# backplane.net
KiCad netlist of a schematic drawn in EAGLE
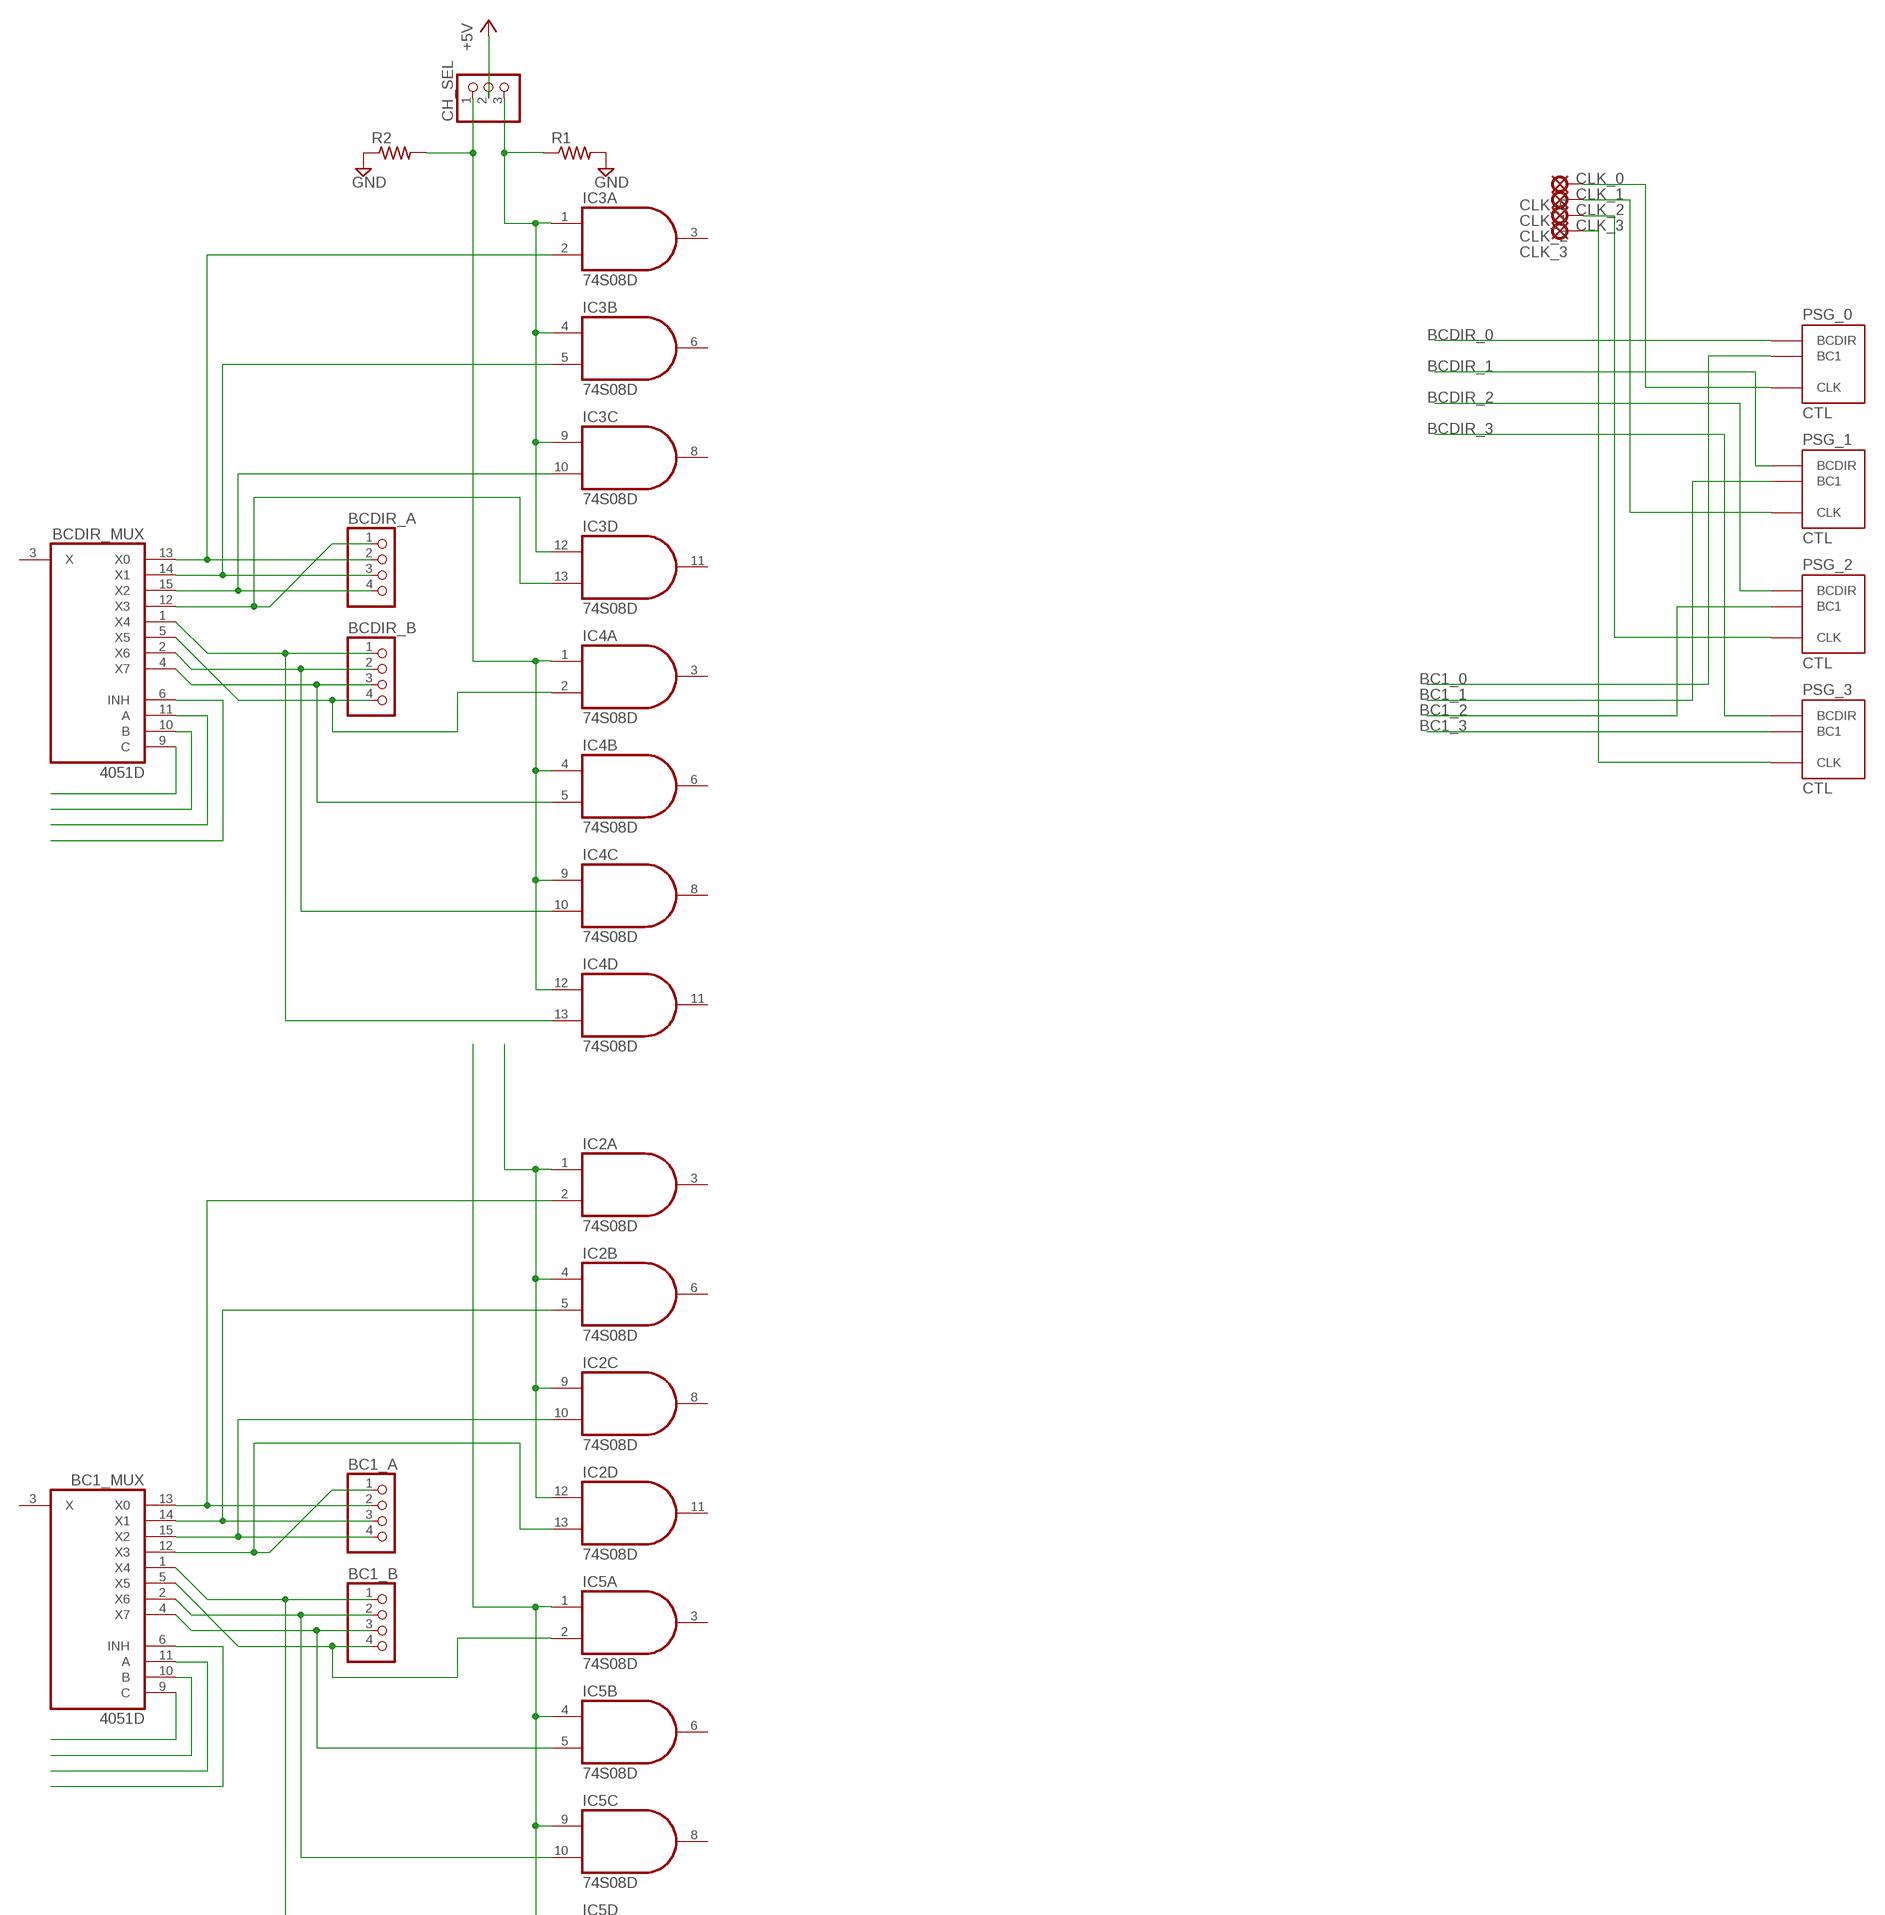
[diagram p0: schematic, sheet 1, part 1 of 3]
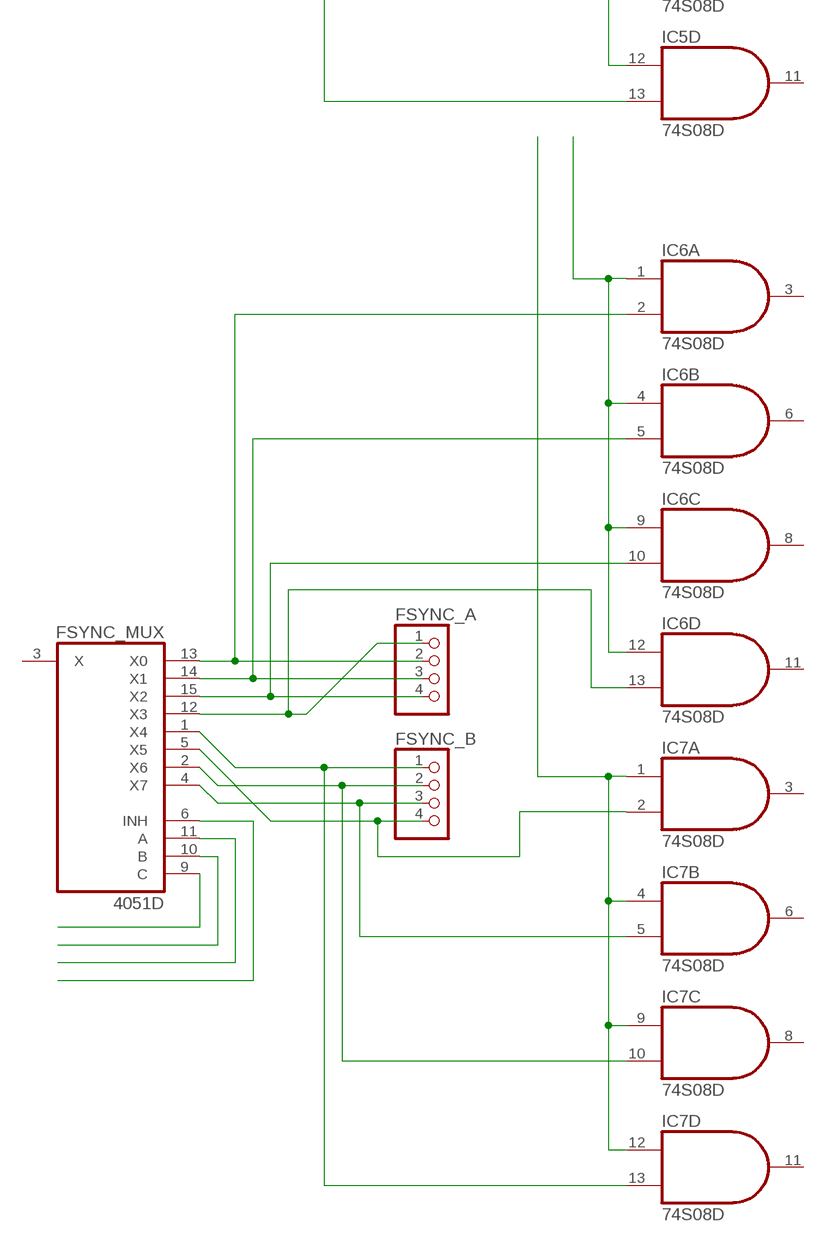
[diagram p1: schematic, sheet 1, part 2 of 3]
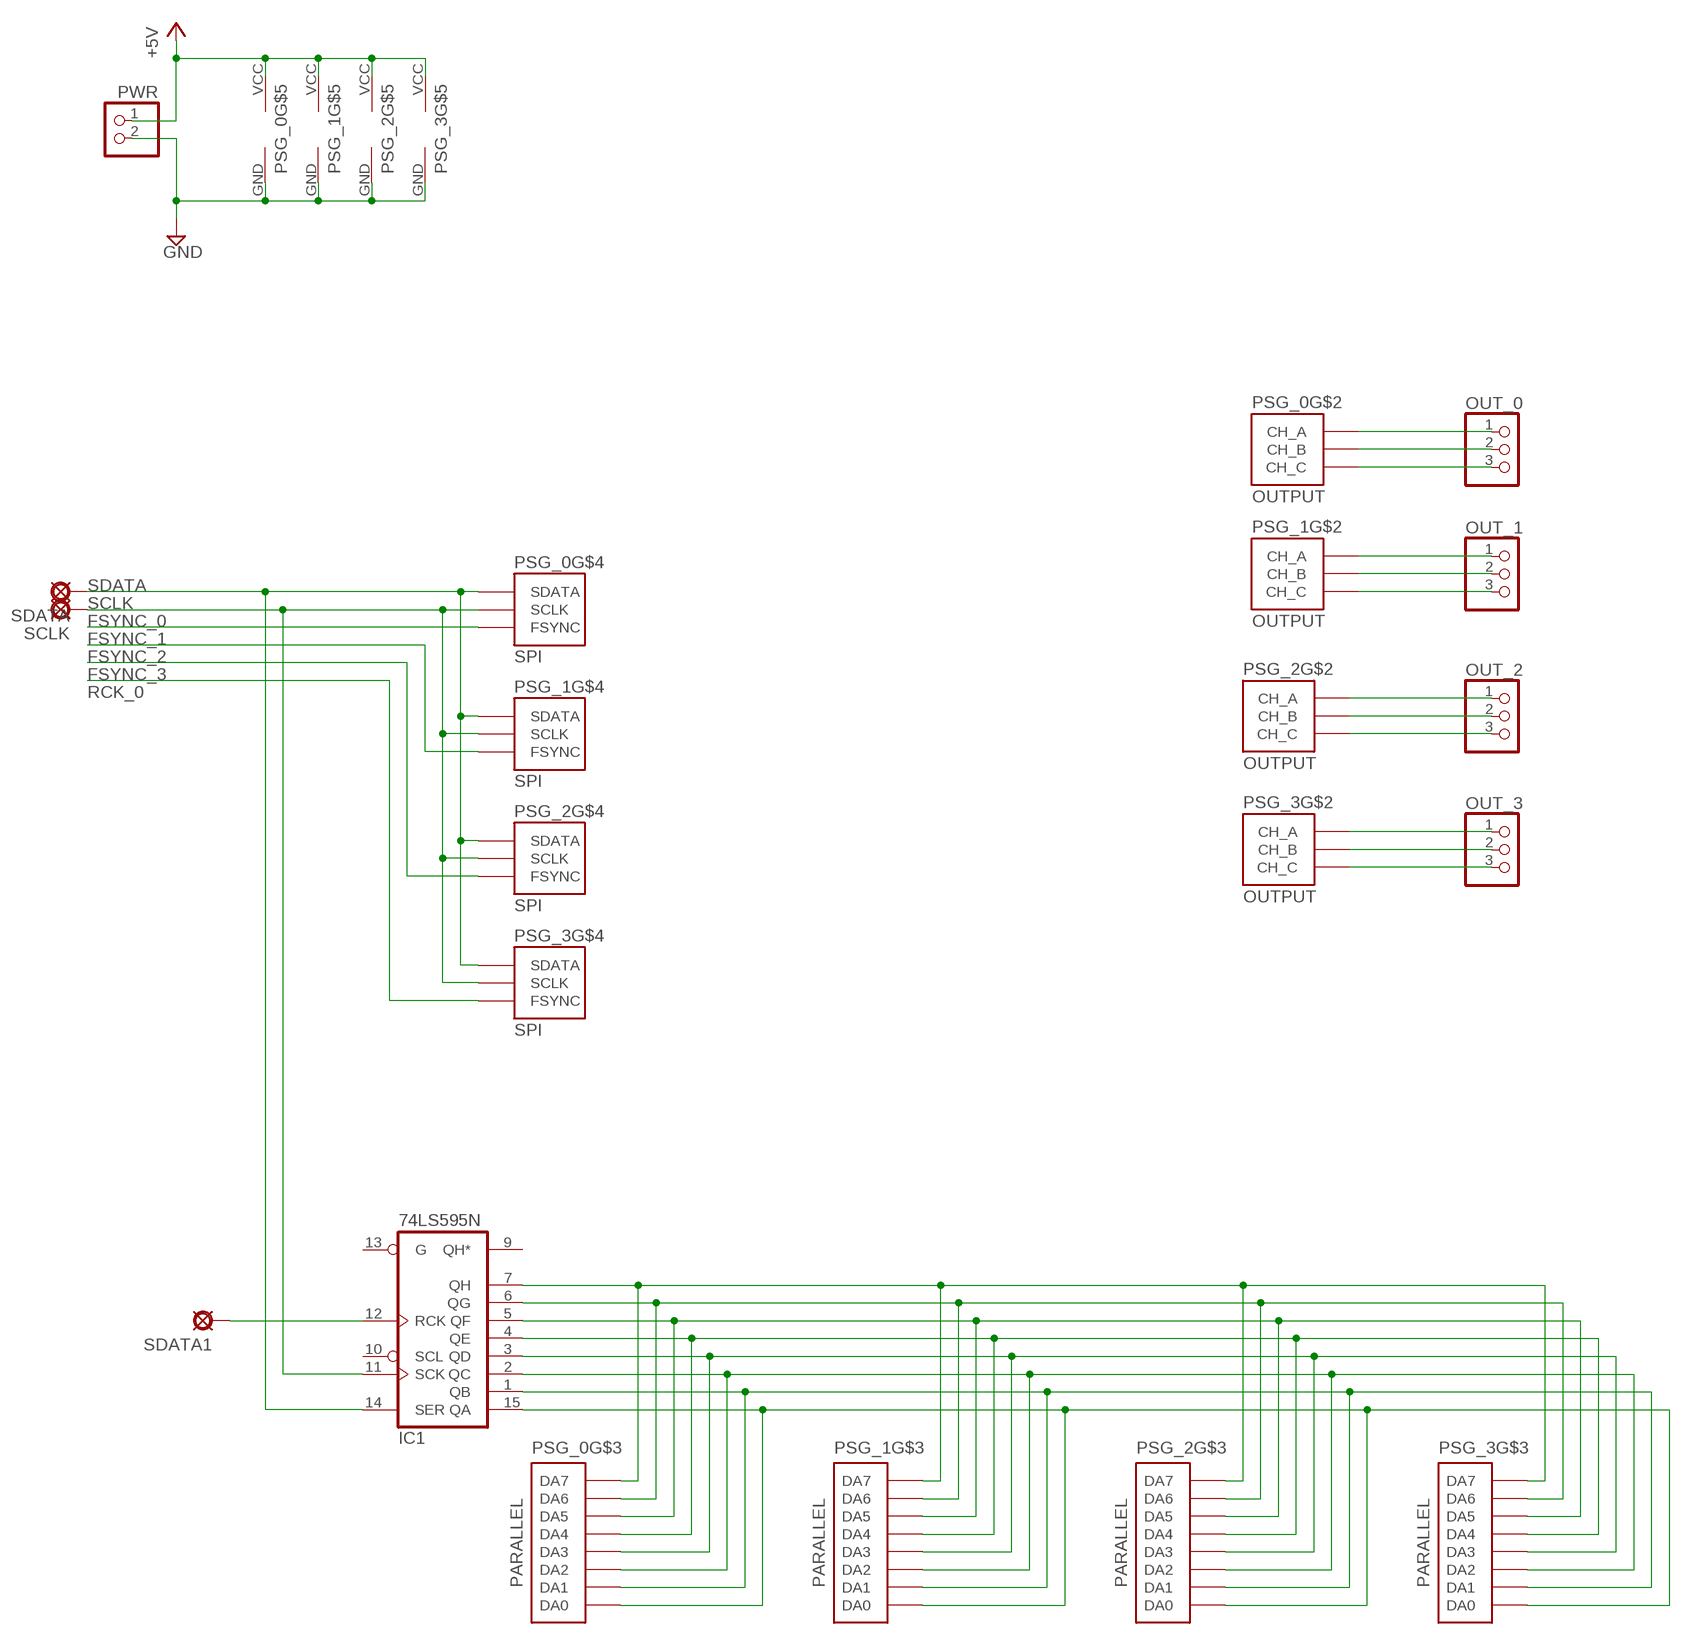
[diagram p2: schematic, sheet 1, part 3 of 3]

(export (version "E")
  (design (tool "Eeschema 10.0.6"))
  (components
    (comp (ref "BC1_A")
      (value "PINHD-1X4")
      (footprint "eagle-import:1X04")
      (libsource (lib "eagle-import") (part "PINHD-1X4"))
    )
    (comp (ref "BC1_B")
      (value "PINHD-1X4")
      (footprint "eagle-import:1X04")
      (libsource (lib "eagle-import") (part "PINHD-1X4"))
    )
    (comp (ref "BC1_MUX")
      (value "4051D")
      (footprint "eagle-import:SO16")
      (libsource (lib "eagle-import") (part "4051D"))
    )
    (comp (ref "BCDIR_A")
      (value "PINHD-1X4")
      (footprint "eagle-import:1X04")
      (libsource (lib "eagle-import") (part "PINHD-1X4"))
    )
    (comp (ref "BCDIR_B")
      (value "PINHD-1X4")
      (footprint "eagle-import:1X04")
      (libsource (lib "eagle-import") (part "PINHD-1X4"))
    )
    (comp (ref "BCDIR_MUX")
      (value "4051D")
      (footprint "eagle-import:SO16")
      (libsource (lib "eagle-import") (part "4051D"))
    )
    (comp (ref "CH_SEL")
      (value "PINHD-1X3")
      (footprint "eagle-import:1X03")
      (libsource (lib "eagle-import") (part "PINHD-1X3"))
    )
    (comp (ref "CLK_0")
      (value "PAD")
      (footprint "eagle-import:SQUARE")
      (libsource (lib "eagle-import") (part "PAD"))
    )
    (comp (ref "CLK_1")
      (value "PAD")
      (footprint "eagle-import:SQUARE")
      (libsource (lib "eagle-import") (part "PAD"))
    )
    (comp (ref "CLK_2")
      (value "PAD")
      (footprint "eagle-import:SQUARE")
      (libsource (lib "eagle-import") (part "PAD"))
    )
    (comp (ref "CLK_3")
      (value "PAD")
      (footprint "eagle-import:SQUARE")
      (libsource (lib "eagle-import") (part "PAD"))
    )
    (comp (ref "FSYNC_A")
      (value "PINHD-1X4")
      (footprint "eagle-import:1X04")
      (libsource (lib "eagle-import") (part "PINHD-1X4"))
    )
    (comp (ref "FSYNC_B")
      (value "PINHD-1X4")
      (footprint "eagle-import:1X04")
      (libsource (lib "eagle-import") (part "PINHD-1X4"))
    )
    (comp (ref "FSYNC_MUX")
      (value "4051D")
      (footprint "eagle-import:SO16")
      (libsource (lib "eagle-import") (part "4051D"))
    )
    (comp (ref "IC1")
      (value "74LS595N")
      (footprint "eagle-import:DIL16")
      (libsource (lib "eagle-import") (part "74595NLS"))
    )
    (comp (ref "IC2")
      (value "74S08D")
      (footprint "eagle-import:SO14")
      (libsource (lib "eagle-import") (part "7408DS"))
    )
    (comp (ref "IC3")
      (value "74S08D")
      (footprint "eagle-import:SO14")
      (libsource (lib "eagle-import") (part "7408DS"))
    )
    (comp (ref "IC4")
      (value "74S08D")
      (footprint "eagle-import:SO14")
      (libsource (lib "eagle-import") (part "7408DS"))
    )
    (comp (ref "IC5")
      (value "74S08D")
      (footprint "eagle-import:SO14")
      (libsource (lib "eagle-import") (part "7408DS"))
    )
    (comp (ref "IC6")
      (value "74S08D")
      (footprint "eagle-import:SO14")
      (libsource (lib "eagle-import") (part "7408DS"))
    )
    (comp (ref "IC7")
      (value "74S08D")
      (footprint "eagle-import:SO14")
      (libsource (lib "eagle-import") (part "7408DS"))
    )
    (comp (ref "OUT_0")
      (value "PINHD-1X3")
      (footprint "eagle-import:1X03")
      (libsource (lib "eagle-import") (part "PINHD-1X3"))
    )
    (comp (ref "OUT_1")
      (value "PINHD-1X3")
      (footprint "eagle-import:1X03")
      (libsource (lib "eagle-import") (part "PINHD-1X3"))
    )
    (comp (ref "OUT_2")
      (value "PINHD-1X3")
      (footprint "eagle-import:1X03")
      (libsource (lib "eagle-import") (part "PINHD-1X3"))
    )
    (comp (ref "OUT_3")
      (value "PINHD-1X3")
      (footprint "eagle-import:1X03")
      (libsource (lib "eagle-import") (part "PINHD-1X3"))
    )
    (comp (ref "PSG_0")
      (value "PSG_DAUGHTER")
      (footprint "eagle-import:PSG_DAUGHTER")
      (libsource (lib "eagle-import") (part "PSG_DAUGHTER"))
    )
    (comp (ref "PSG_1")
      (value "PSG_DAUGHTER")
      (footprint "eagle-import:PSG_DAUGHTER")
      (libsource (lib "eagle-import") (part "PSG_DAUGHTER"))
    )
    (comp (ref "PSG_2")
      (value "PSG_DAUGHTER")
      (footprint "eagle-import:PSG_DAUGHTER")
      (libsource (lib "eagle-import") (part "PSG_DAUGHTER"))
    )
    (comp (ref "PSG_3")
      (value "PSG_DAUGHTER")
      (footprint "eagle-import:PSG_DAUGHTER")
      (libsource (lib "eagle-import") (part "PSG_DAUGHTER"))
    )
    (comp (ref "PWR")
      (value "PINHD-1X2")
      (footprint "eagle-import:1X02")
      (libsource (lib "eagle-import") (part "PINHD-1X2"))
    )
    (comp (ref "R1")
      (value "6MM.3")
      (footprint "eagle-import:R0207_3")
      (libsource (lib "eagle-import") (part "6MM.3"))
    )
    (comp (ref "R2")
      (value "6MM.3")
      (footprint "eagle-import:R0207_3")
      (libsource (lib "eagle-import") (part "6MM.3"))
    )
    (comp (ref "SCLK")
      (value "PAD")
      (footprint "eagle-import:SQUARE")
      (libsource (lib "eagle-import") (part "PAD"))
    )
    (comp (ref "SDATA")
      (value "PAD")
      (footprint "eagle-import:SQUARE")
      (libsource (lib "eagle-import") (part "PAD"))
    )
    (comp (ref "SDATA1")
      (value "PAD")
      (footprint "eagle-import:SQUARE")
      (libsource (lib "eagle-import") (part "PAD"))
    )
  )
  (nets
    (net (code "1") (name "+5V") (class "Default")
      (node (ref "CH_SEL") (pin "2") (pinfunction "2_2") (pintype "passive"))
      (node (ref "PSG_0") (pin "VCC") (pinfunction "VCC_VCC") (pintype "power_in"))
      (node (ref "PSG_1") (pin "VCC") (pinfunction "VCC_VCC") (pintype "power_in"))
      (node (ref "PSG_2") (pin "VCC") (pinfunction "VCC_VCC") (pintype "power_in"))
      (node (ref "PSG_3") (pin "VCC") (pinfunction "VCC_VCC") (pintype "power_in"))
      (node (ref "PWR") (pin "1") (pinfunction "1_1") (pintype "passive"))
    )
    (net (code "2") (name "/BC1_0") (class "Default")
      (node (ref "PSG_0") (pin "BC1") (pinfunction "BC1_BC1") (pintype "input"))
    )
    (net (code "3") (name "/BC1_1") (class "Default")
      (node (ref "PSG_1") (pin "BC1") (pinfunction "BC1_BC1") (pintype "input"))
    )
    (net (code "4") (name "/BC1_2") (class "Default")
      (node (ref "PSG_2") (pin "BC1") (pinfunction "BC1_BC1") (pintype "input"))
    )
    (net (code "5") (name "/BC1_3") (class "Default")
      (node (ref "PSG_3") (pin "BC1") (pinfunction "BC1_BC1") (pintype "input"))
    )
    (net (code "6") (name "/BCDIR_0") (class "Default")
      (node (ref "PSG_0") (pin "BCDIR") (pinfunction "BCDIR_BCDIR") (pintype "input"))
    )
    (net (code "7") (name "/BCDIR_1") (class "Default")
      (node (ref "PSG_1") (pin "BCDIR") (pinfunction "BCDIR_BCDIR") (pintype "input"))
    )
    (net (code "8") (name "/BCDIR_2") (class "Default")
      (node (ref "PSG_2") (pin "BCDIR") (pinfunction "BCDIR_BCDIR") (pintype "input"))
    )
    (net (code "9") (name "/BCDIR_3") (class "Default")
      (node (ref "PSG_3") (pin "BCDIR") (pinfunction "BCDIR_BCDIR") (pintype "input"))
    )
    (net (code "10") (name "/CH_A") (class "Default")
      (node (ref "CH_SEL") (pin "3") (pinfunction "3_3") (pintype "passive"))
      (node (ref "IC2") (pin "1") (pinfunction "I0_1") (pintype "input"))
      (node (ref "IC2") (pin "12") (pinfunction "I0_12") (pintype "input"))
      (node (ref "IC2") (pin "4") (pinfunction "I0_4") (pintype "input"))
      (node (ref "IC2") (pin "9") (pinfunction "I0_9") (pintype "input"))
      (node (ref "IC3") (pin "1") (pinfunction "I0_1") (pintype "input"))
      (node (ref "IC3") (pin "12") (pinfunction "I0_12") (pintype "input"))
      (node (ref "IC3") (pin "4") (pinfunction "I0_4") (pintype "input"))
      (node (ref "IC3") (pin "9") (pinfunction "I0_9") (pintype "input"))
      (node (ref "IC6") (pin "1") (pinfunction "I0_1") (pintype "input"))
      (node (ref "IC6") (pin "12") (pinfunction "I0_12") (pintype "input"))
      (node (ref "IC6") (pin "4") (pinfunction "I0_4") (pintype "input"))
      (node (ref "IC6") (pin "9") (pinfunction "I0_9") (pintype "input"))
      (node (ref "R1") (pin "1") (pinfunction "1_1") (pintype "passive"))
    )
    (net (code "11") (name "/CH_B") (class "Default")
      (node (ref "CH_SEL") (pin "1") (pinfunction "1_1") (pintype "passive"))
      (node (ref "IC4") (pin "1") (pinfunction "I0_1") (pintype "input"))
      (node (ref "IC4") (pin "12") (pinfunction "I0_12") (pintype "input"))
      (node (ref "IC4") (pin "4") (pinfunction "I0_4") (pintype "input"))
      (node (ref "IC4") (pin "9") (pinfunction "I0_9") (pintype "input"))
      (node (ref "IC5") (pin "1") (pinfunction "I0_1") (pintype "input"))
      (node (ref "IC5") (pin "12") (pinfunction "I0_12") (pintype "input"))
      (node (ref "IC5") (pin "4") (pinfunction "I0_4") (pintype "input"))
      (node (ref "IC5") (pin "9") (pinfunction "I0_9") (pintype "input"))
      (node (ref "IC7") (pin "1") (pinfunction "I0_1") (pintype "input"))
      (node (ref "IC7") (pin "12") (pinfunction "I0_12") (pintype "input"))
      (node (ref "IC7") (pin "4") (pinfunction "I0_4") (pintype "input"))
      (node (ref "IC7") (pin "9") (pinfunction "I0_9") (pintype "input"))
      (node (ref "R2") (pin "2") (pinfunction "2_2") (pintype "passive"))
    )
    (net (code "12") (name "/CLK_0") (class "Default")
      (node (ref "CLK_0") (pin "1") (pinfunction "PAD_1") (pintype "passive"))
      (node (ref "PSG_0") (pin "CLK") (pinfunction "CLK_CLK") (pintype "input"))
    )
    (net (code "13") (name "/CLK_1") (class "Default")
      (node (ref "CLK_1") (pin "1") (pinfunction "PAD_1") (pintype "passive"))
      (node (ref "PSG_1") (pin "CLK") (pinfunction "CLK_CLK") (pintype "input"))
    )
    (net (code "14") (name "/CLK_2") (class "Default")
      (node (ref "CLK_2") (pin "1") (pinfunction "PAD_1") (pintype "passive"))
      (node (ref "PSG_2") (pin "CLK") (pinfunction "CLK_CLK") (pintype "input"))
    )
    (net (code "15") (name "/CLK_3") (class "Default")
      (node (ref "CLK_3") (pin "1") (pinfunction "PAD_1") (pintype "passive"))
      (node (ref "PSG_3") (pin "CLK") (pinfunction "CLK_CLK") (pintype "input"))
    )
    (net (code "16") (name "/FSYNC_0") (class "Default")
      (node (ref "PSG_0") (pin "FSYNC") (pinfunction "FSYNC_FSYNC") (pintype "input"))
    )
    (net (code "17") (name "/FSYNC_1") (class "Default")
      (node (ref "PSG_1") (pin "FSYNC") (pinfunction "FSYNC_FSYNC") (pintype "input"))
    )
    (net (code "18") (name "/FSYNC_2") (class "Default")
      (node (ref "PSG_2") (pin "FSYNC") (pinfunction "FSYNC_FSYNC") (pintype "input"))
    )
    (net (code "19") (name "/FSYNC_3") (class "Default")
      (node (ref "PSG_3") (pin "FSYNC") (pinfunction "FSYNC_FSYNC") (pintype "input"))
    )
    (net (code "20") (name "/RCK_0") (class "Default")
      (node (ref "IC1") (pin "12") (pinfunction "RCK_12") (pintype "input"))
      (node (ref "SDATA1") (pin "1") (pinfunction "PAD_1") (pintype "passive"))
    )
    (net (code "21") (name "/SCLK") (class "Default")
      (node (ref "IC1") (pin "11") (pinfunction "SCK_11") (pintype "input"))
      (node (ref "PSG_0") (pin "SCLK") (pinfunction "SCLK_SCLK") (pintype "input"))
      (node (ref "PSG_1") (pin "SCLK") (pinfunction "SCLK_SCLK") (pintype "input"))
      (node (ref "PSG_2") (pin "SCLK") (pinfunction "SCLK_SCLK") (pintype "input"))
      (node (ref "PSG_3") (pin "SCLK") (pinfunction "SCLK_SCLK") (pintype "input"))
      (node (ref "SCLK") (pin "1") (pinfunction "PAD_1") (pintype "passive"))
    )
    (net (code "22") (name "/SDATA") (class "Default")
      (node (ref "IC1") (pin "14") (pinfunction "SER_14") (pintype "input"))
      (node (ref "PSG_0") (pin "SDATA") (pinfunction "SDATA_SDATA") (pintype "bidirectional"))
      (node (ref "PSG_1") (pin "SDATA") (pinfunction "SDATA_SDATA") (pintype "bidirectional"))
      (node (ref "PSG_2") (pin "SDATA") (pinfunction "SDATA_SDATA") (pintype "bidirectional"))
      (node (ref "PSG_3") (pin "SDATA") (pinfunction "SDATA_SDATA") (pintype "bidirectional"))
      (node (ref "SDATA") (pin "1") (pinfunction "PAD_1") (pintype "passive"))
    )
    (net (code "23") (name "GND") (class "Default")
      (node (ref "PSG_0") (pin "GND") (pinfunction "GND_GND") (pintype "power_in"))
      (node (ref "PSG_1") (pin "GND") (pinfunction "GND_GND") (pintype "power_in"))
      (node (ref "PSG_2") (pin "GND") (pinfunction "GND_GND") (pintype "power_in"))
      (node (ref "PSG_3") (pin "GND") (pinfunction "GND_GND") (pintype "power_in"))
      (node (ref "PWR") (pin "2") (pinfunction "2_2") (pintype "passive"))
      (node (ref "R1") (pin "2") (pinfunction "2_2") (pintype "passive"))
      (node (ref "R2") (pin "1") (pinfunction "1_1") (pintype "passive"))
    )
    (net (code "24") (name "Net-(BC1_MUXA-X0)") (class "Default")
      (node (ref "BC1_A") (pin "2") (pinfunction "2_2") (pintype "passive"))
      (node (ref "BC1_MUX") (pin "13") (pinfunction "X0_13") (pintype "bidirectional"))
      (node (ref "IC2") (pin "2") (pinfunction "I1_2") (pintype "input"))
    )
    (net (code "25") (name "Net-(BC1_MUXA-X1)") (class "Default")
      (node (ref "BC1_A") (pin "3") (pinfunction "3_3") (pintype "passive"))
      (node (ref "BC1_MUX") (pin "14") (pinfunction "X1_14") (pintype "bidirectional"))
      (node (ref "IC2") (pin "5") (pinfunction "I1_5") (pintype "input"))
    )
    (net (code "26") (name "Net-(BC1_MUXA-X2)") (class "Default")
      (node (ref "BC1_A") (pin "4") (pinfunction "4_4") (pintype "passive"))
      (node (ref "BC1_MUX") (pin "15") (pinfunction "X2_15") (pintype "bidirectional"))
      (node (ref "IC2") (pin "10") (pinfunction "I1_10") (pintype "input"))
    )
    (net (code "27") (name "Net-(BC1_MUXA-X3)") (class "Default")
      (node (ref "BC1_A") (pin "1") (pinfunction "1_1") (pintype "passive"))
      (node (ref "BC1_MUX") (pin "12") (pinfunction "X3_12") (pintype "bidirectional"))
      (node (ref "IC2") (pin "13") (pinfunction "I1_13") (pintype "input"))
    )
    (net (code "28") (name "Net-(BC1_MUXA-X4)") (class "Default")
      (node (ref "BC1_B") (pin "1") (pinfunction "1_1") (pintype "passive"))
      (node (ref "BC1_MUX") (pin "1") (pinfunction "X4_1") (pintype "bidirectional"))
      (node (ref "IC5") (pin "13") (pinfunction "I1_13") (pintype "input"))
    )
    (net (code "29") (name "Net-(BC1_MUXA-X5)") (class "Default")
      (node (ref "BC1_B") (pin "4") (pinfunction "4_4") (pintype "passive"))
      (node (ref "BC1_MUX") (pin "5") (pinfunction "X5_5") (pintype "bidirectional"))
      (node (ref "IC5") (pin "2") (pinfunction "I1_2") (pintype "input"))
    )
    (net (code "30") (name "Net-(BC1_MUXA-X6)") (class "Default")
      (node (ref "BC1_B") (pin "2") (pinfunction "2_2") (pintype "passive"))
      (node (ref "BC1_MUX") (pin "2") (pinfunction "X6_2") (pintype "bidirectional"))
      (node (ref "IC5") (pin "10") (pinfunction "I1_10") (pintype "input"))
    )
    (net (code "31") (name "Net-(BC1_MUXA-X7)") (class "Default")
      (node (ref "BC1_B") (pin "3") (pinfunction "3_3") (pintype "passive"))
      (node (ref "BC1_MUX") (pin "4") (pinfunction "X7_4") (pintype "bidirectional"))
      (node (ref "IC5") (pin "5") (pinfunction "I1_5") (pintype "input"))
    )
    (net (code "32") (name "Net-(BCDIR_MUXA-X0)") (class "Default")
      (node (ref "BCDIR_A") (pin "2") (pinfunction "2_2") (pintype "passive"))
      (node (ref "BCDIR_MUX") (pin "13") (pinfunction "X0_13") (pintype "bidirectional"))
      (node (ref "IC3") (pin "2") (pinfunction "I1_2") (pintype "input"))
    )
    (net (code "33") (name "Net-(BCDIR_MUXA-X1)") (class "Default")
      (node (ref "BCDIR_A") (pin "3") (pinfunction "3_3") (pintype "passive"))
      (node (ref "BCDIR_MUX") (pin "14") (pinfunction "X1_14") (pintype "bidirectional"))
      (node (ref "IC3") (pin "5") (pinfunction "I1_5") (pintype "input"))
    )
    (net (code "34") (name "Net-(BCDIR_MUXA-X2)") (class "Default")
      (node (ref "BCDIR_A") (pin "4") (pinfunction "4_4") (pintype "passive"))
      (node (ref "BCDIR_MUX") (pin "15") (pinfunction "X2_15") (pintype "bidirectional"))
      (node (ref "IC3") (pin "10") (pinfunction "I1_10") (pintype "input"))
    )
    (net (code "35") (name "Net-(BCDIR_MUXA-X3)") (class "Default")
      (node (ref "BCDIR_A") (pin "1") (pinfunction "1_1") (pintype "passive"))
      (node (ref "BCDIR_MUX") (pin "12") (pinfunction "X3_12") (pintype "bidirectional"))
      (node (ref "IC3") (pin "13") (pinfunction "I1_13") (pintype "input"))
    )
    (net (code "36") (name "Net-(BCDIR_MUXA-X4)") (class "Default")
      (node (ref "BCDIR_B") (pin "1") (pinfunction "1_1") (pintype "passive"))
      (node (ref "BCDIR_MUX") (pin "1") (pinfunction "X4_1") (pintype "bidirectional"))
      (node (ref "IC4") (pin "13") (pinfunction "I1_13") (pintype "input"))
    )
    (net (code "37") (name "Net-(BCDIR_MUXA-X5)") (class "Default")
      (node (ref "BCDIR_B") (pin "4") (pinfunction "4_4") (pintype "passive"))
      (node (ref "BCDIR_MUX") (pin "5") (pinfunction "X5_5") (pintype "bidirectional"))
      (node (ref "IC4") (pin "2") (pinfunction "I1_2") (pintype "input"))
    )
    (net (code "38") (name "Net-(BCDIR_MUXA-X6)") (class "Default")
      (node (ref "BCDIR_B") (pin "2") (pinfunction "2_2") (pintype "passive"))
      (node (ref "BCDIR_MUX") (pin "2") (pinfunction "X6_2") (pintype "bidirectional"))
      (node (ref "IC4") (pin "10") (pinfunction "I1_10") (pintype "input"))
    )
    (net (code "39") (name "Net-(BCDIR_MUXA-X7)") (class "Default")
      (node (ref "BCDIR_B") (pin "3") (pinfunction "3_3") (pintype "passive"))
      (node (ref "BCDIR_MUX") (pin "4") (pinfunction "X7_4") (pintype "bidirectional"))
      (node (ref "IC4") (pin "5") (pinfunction "I1_5") (pintype "input"))
    )
    (net (code "40") (name "Net-(FSYNC_MUXA-X0)") (class "Default")
      (node (ref "FSYNC_A") (pin "2") (pinfunction "2_2") (pintype "passive"))
      (node (ref "FSYNC_MUX") (pin "13") (pinfunction "X0_13") (pintype "bidirectional"))
      (node (ref "IC6") (pin "2") (pinfunction "I1_2") (pintype "input"))
    )
    (net (code "41") (name "Net-(FSYNC_MUXA-X1)") (class "Default")
      (node (ref "FSYNC_A") (pin "3") (pinfunction "3_3") (pintype "passive"))
      (node (ref "FSYNC_MUX") (pin "14") (pinfunction "X1_14") (pintype "bidirectional"))
      (node (ref "IC6") (pin "5") (pinfunction "I1_5") (pintype "input"))
    )
    (net (code "42") (name "Net-(FSYNC_MUXA-X2)") (class "Default")
      (node (ref "FSYNC_A") (pin "4") (pinfunction "4_4") (pintype "passive"))
      (node (ref "FSYNC_MUX") (pin "15") (pinfunction "X2_15") (pintype "bidirectional"))
      (node (ref "IC6") (pin "10") (pinfunction "I1_10") (pintype "input"))
    )
    (net (code "43") (name "Net-(FSYNC_MUXA-X3)") (class "Default")
      (node (ref "FSYNC_A") (pin "1") (pinfunction "1_1") (pintype "passive"))
      (node (ref "FSYNC_MUX") (pin "12") (pinfunction "X3_12") (pintype "bidirectional"))
      (node (ref "IC6") (pin "13") (pinfunction "I1_13") (pintype "input"))
    )
    (net (code "44") (name "Net-(FSYNC_MUXA-X4)") (class "Default")
      (node (ref "FSYNC_B") (pin "1") (pinfunction "1_1") (pintype "passive"))
      (node (ref "FSYNC_MUX") (pin "1") (pinfunction "X4_1") (pintype "bidirectional"))
      (node (ref "IC7") (pin "13") (pinfunction "I1_13") (pintype "input"))
    )
    (net (code "45") (name "Net-(FSYNC_MUXA-X5)") (class "Default")
      (node (ref "FSYNC_B") (pin "4") (pinfunction "4_4") (pintype "passive"))
      (node (ref "FSYNC_MUX") (pin "5") (pinfunction "X5_5") (pintype "bidirectional"))
      (node (ref "IC7") (pin "2") (pinfunction "I1_2") (pintype "input"))
    )
    (net (code "46") (name "Net-(FSYNC_MUXA-X6)") (class "Default")
      (node (ref "FSYNC_B") (pin "2") (pinfunction "2_2") (pintype "passive"))
      (node (ref "FSYNC_MUX") (pin "2") (pinfunction "X6_2") (pintype "bidirectional"))
      (node (ref "IC7") (pin "10") (pinfunction "I1_10") (pintype "input"))
    )
    (net (code "47") (name "Net-(FSYNC_MUXA-X7)") (class "Default")
      (node (ref "FSYNC_B") (pin "3") (pinfunction "3_3") (pintype "passive"))
      (node (ref "FSYNC_MUX") (pin "4") (pinfunction "X7_4") (pintype "bidirectional"))
      (node (ref "IC7") (pin "5") (pinfunction "I1_5") (pintype "input"))
    )
    (net (code "48") (name "Net-(IC1A-QA)") (class "Default")
      (node (ref "IC1") (pin "15") (pinfunction "QA_15") (pintype "tri_state"))
      (node (ref "PSG_0") (pin "DA0") (pinfunction "DA0_DA0") (pintype "bidirectional"))
      (node (ref "PSG_1") (pin "DA0") (pinfunction "DA0_DA0") (pintype "bidirectional"))
      (node (ref "PSG_2") (pin "DA0") (pinfunction "DA0_DA0") (pintype "bidirectional"))
      (node (ref "PSG_3") (pin "DA0") (pinfunction "DA0_DA0") (pintype "bidirectional"))
    )
    (net (code "49") (name "Net-(IC1A-QB)") (class "Default")
      (node (ref "IC1") (pin "1") (pinfunction "QB_1") (pintype "tri_state"))
      (node (ref "PSG_0") (pin "DA1") (pinfunction "DA1_DA1") (pintype "bidirectional"))
      (node (ref "PSG_1") (pin "DA1") (pinfunction "DA1_DA1") (pintype "bidirectional"))
      (node (ref "PSG_2") (pin "DA1") (pinfunction "DA1_DA1") (pintype "bidirectional"))
      (node (ref "PSG_3") (pin "DA1") (pinfunction "DA1_DA1") (pintype "bidirectional"))
    )
    (net (code "50") (name "Net-(IC1A-QC)") (class "Default")
      (node (ref "IC1") (pin "2") (pinfunction "QC_2") (pintype "tri_state"))
      (node (ref "PSG_0") (pin "DA2") (pinfunction "DA2_DA2") (pintype "bidirectional"))
      (node (ref "PSG_1") (pin "DA2") (pinfunction "DA2_DA2") (pintype "bidirectional"))
      (node (ref "PSG_2") (pin "DA2") (pinfunction "DA2_DA2") (pintype "bidirectional"))
      (node (ref "PSG_3") (pin "DA2") (pinfunction "DA2_DA2") (pintype "bidirectional"))
    )
    (net (code "51") (name "Net-(IC1A-QD)") (class "Default")
      (node (ref "IC1") (pin "3") (pinfunction "QD_3") (pintype "tri_state"))
      (node (ref "PSG_0") (pin "DA3") (pinfunction "DA3_DA3") (pintype "bidirectional"))
      (node (ref "PSG_1") (pin "DA3") (pinfunction "DA3_DA3") (pintype "bidirectional"))
      (node (ref "PSG_2") (pin "DA3") (pinfunction "DA3_DA3") (pintype "bidirectional"))
      (node (ref "PSG_3") (pin "DA3") (pinfunction "DA3_DA3") (pintype "bidirectional"))
    )
    (net (code "52") (name "Net-(IC1A-QE)") (class "Default")
      (node (ref "IC1") (pin "4") (pinfunction "QE_4") (pintype "tri_state"))
      (node (ref "PSG_0") (pin "DA4") (pinfunction "DA4_DA4") (pintype "bidirectional"))
      (node (ref "PSG_1") (pin "DA4") (pinfunction "DA4_DA4") (pintype "bidirectional"))
      (node (ref "PSG_2") (pin "DA4") (pinfunction "DA4_DA4") (pintype "bidirectional"))
      (node (ref "PSG_3") (pin "DA4") (pinfunction "DA4_DA4") (pintype "bidirectional"))
    )
    (net (code "53") (name "Net-(IC1A-QF)") (class "Default")
      (node (ref "IC1") (pin "5") (pinfunction "QF_5") (pintype "tri_state"))
      (node (ref "PSG_0") (pin "DA5") (pinfunction "DA5_DA5") (pintype "bidirectional"))
      (node (ref "PSG_1") (pin "DA5") (pinfunction "DA5_DA5") (pintype "bidirectional"))
      (node (ref "PSG_2") (pin "DA5") (pinfunction "DA5_DA5") (pintype "bidirectional"))
      (node (ref "PSG_3") (pin "DA5") (pinfunction "DA5_DA5") (pintype "bidirectional"))
    )
    (net (code "54") (name "Net-(IC1A-QG)") (class "Default")
      (node (ref "IC1") (pin "6") (pinfunction "QG_6") (pintype "tri_state"))
      (node (ref "PSG_0") (pin "DA6") (pinfunction "DA6_DA6") (pintype "bidirectional"))
      (node (ref "PSG_1") (pin "DA6") (pinfunction "DA6_DA6") (pintype "bidirectional"))
      (node (ref "PSG_2") (pin "DA6") (pinfunction "DA6_DA6") (pintype "bidirectional"))
      (node (ref "PSG_3") (pin "DA6") (pinfunction "DA6_DA6") (pintype "bidirectional"))
    )
    (net (code "55") (name "Net-(IC1A-QH)") (class "Default")
      (node (ref "IC1") (pin "7") (pinfunction "QH_7") (pintype "tri_state"))
      (node (ref "PSG_0") (pin "DA7") (pinfunction "DA7_DA7") (pintype "bidirectional"))
      (node (ref "PSG_1") (pin "DA7") (pinfunction "DA7_DA7") (pintype "bidirectional"))
      (node (ref "PSG_2") (pin "DA7") (pinfunction "DA7_DA7") (pintype "bidirectional"))
      (node (ref "PSG_3") (pin "DA7") (pinfunction "DA7_DA7") (pintype "bidirectional"))
    )
    (net (code "56") (name "Net-(PSG_0B-CH_A)") (class "Default")
      (node (ref "OUT_0") (pin "1") (pinfunction "1_1") (pintype "passive"))
      (node (ref "PSG_0") (pin "OUT_A") (pinfunction "CH_A_OUT_A") (pintype "input"))
    )
    (net (code "57") (name "Net-(PSG_0B-CH_B)") (class "Default")
      (node (ref "OUT_0") (pin "2") (pinfunction "2_2") (pintype "passive"))
      (node (ref "PSG_0") (pin "OUT_B") (pinfunction "CH_B_OUT_B") (pintype "input"))
    )
    (net (code "58") (name "Net-(PSG_0B-CH_C)") (class "Default")
      (node (ref "OUT_0") (pin "3") (pinfunction "3_3") (pintype "passive"))
      (node (ref "PSG_0") (pin "OUT_C") (pinfunction "CH_C_OUT_C") (pintype "input"))
    )
    (net (code "59") (name "Net-(PSG_1B-CH_A)") (class "Default")
      (node (ref "OUT_1") (pin "1") (pinfunction "1_1") (pintype "passive"))
      (node (ref "PSG_1") (pin "OUT_A") (pinfunction "CH_A_OUT_A") (pintype "input"))
    )
    (net (code "60") (name "Net-(PSG_1B-CH_B)") (class "Default")
      (node (ref "OUT_1") (pin "2") (pinfunction "2_2") (pintype "passive"))
      (node (ref "PSG_1") (pin "OUT_B") (pinfunction "CH_B_OUT_B") (pintype "input"))
    )
    (net (code "61") (name "Net-(PSG_1B-CH_C)") (class "Default")
      (node (ref "OUT_1") (pin "3") (pinfunction "3_3") (pintype "passive"))
      (node (ref "PSG_1") (pin "OUT_C") (pinfunction "CH_C_OUT_C") (pintype "input"))
    )
    (net (code "62") (name "Net-(PSG_2B-CH_A)") (class "Default")
      (node (ref "OUT_2") (pin "1") (pinfunction "1_1") (pintype "passive"))
      (node (ref "PSG_2") (pin "OUT_A") (pinfunction "CH_A_OUT_A") (pintype "input"))
    )
    (net (code "63") (name "Net-(PSG_2B-CH_B)") (class "Default")
      (node (ref "OUT_2") (pin "2") (pinfunction "2_2") (pintype "passive"))
      (node (ref "PSG_2") (pin "OUT_B") (pinfunction "CH_B_OUT_B") (pintype "input"))
    )
    (net (code "64") (name "Net-(PSG_2B-CH_C)") (class "Default")
      (node (ref "OUT_2") (pin "3") (pinfunction "3_3") (pintype "passive"))
      (node (ref "PSG_2") (pin "OUT_C") (pinfunction "CH_C_OUT_C") (pintype "input"))
    )
    (net (code "65") (name "Net-(PSG_3B-CH_A)") (class "Default")
      (node (ref "OUT_3") (pin "1") (pinfunction "1_1") (pintype "passive"))
      (node (ref "PSG_3") (pin "OUT_A") (pinfunction "CH_A_OUT_A") (pintype "input"))
    )
    (net (code "66") (name "Net-(PSG_3B-CH_B)") (class "Default")
      (node (ref "OUT_3") (pin "2") (pinfunction "2_2") (pintype "passive"))
      (node (ref "PSG_3") (pin "OUT_B") (pinfunction "CH_B_OUT_B") (pintype "input"))
    )
    (net (code "67") (name "Net-(PSG_3B-CH_C)") (class "Default")
      (node (ref "OUT_3") (pin "3") (pinfunction "3_3") (pintype "passive"))
      (node (ref "PSG_3") (pin "OUT_C") (pinfunction "CH_C_OUT_C") (pintype "input"))
    )
    (net (code "68") (name "unconnected-(BC1_MUXA-A-Pad11)") (class "Default")
      (node (ref "BC1_MUX") (pin "11") (pinfunction "A_11") (pintype "input"))
    )
    (net (code "69") (name "unconnected-(BC1_MUXA-B-Pad10)") (class "Default")
      (node (ref "BC1_MUX") (pin "10") (pinfunction "B_10") (pintype "input"))
    )
    (net (code "70") (name "unconnected-(BC1_MUXA-C-Pad9)") (class "Default")
      (node (ref "BC1_MUX") (pin "9") (pinfunction "C_9") (pintype "input"))
    )
    (net (code "71") (name "unconnected-(BC1_MUXA-INH-Pad6)") (class "Default")
      (node (ref "BC1_MUX") (pin "6") (pinfunction "INH_6") (pintype "input"))
    )
    (net (code "72") (name "unconnected-(BC1_MUXA-X-Pad3)") (class "Default")
      (node (ref "BC1_MUX") (pin "3") (pinfunction "X_3") (pintype "bidirectional"))
    )
    (net (code "73") (name "unconnected-(BCDIR_MUXA-A-Pad11)") (class "Default")
      (node (ref "BCDIR_MUX") (pin "11") (pinfunction "A_11") (pintype "input"))
    )
    (net (code "74") (name "unconnected-(BCDIR_MUXA-B-Pad10)") (class "Default")
      (node (ref "BCDIR_MUX") (pin "10") (pinfunction "B_10") (pintype "input"))
    )
    (net (code "75") (name "unconnected-(BCDIR_MUXA-C-Pad9)") (class "Default")
      (node (ref "BCDIR_MUX") (pin "9") (pinfunction "C_9") (pintype "input"))
    )
    (net (code "76") (name "unconnected-(BCDIR_MUXA-INH-Pad6)") (class "Default")
      (node (ref "BCDIR_MUX") (pin "6") (pinfunction "INH_6") (pintype "input"))
    )
    (net (code "77") (name "unconnected-(BCDIR_MUXA-X-Pad3)") (class "Default")
      (node (ref "BCDIR_MUX") (pin "3") (pinfunction "X_3") (pintype "bidirectional"))
    )
    (net (code "78") (name "unconnected-(FSYNC_MUXA-A-Pad11)") (class "Default")
      (node (ref "FSYNC_MUX") (pin "11") (pinfunction "A_11") (pintype "input"))
    )
    (net (code "79") (name "unconnected-(FSYNC_MUXA-B-Pad10)") (class "Default")
      (node (ref "FSYNC_MUX") (pin "10") (pinfunction "B_10") (pintype "input"))
    )
    (net (code "80") (name "unconnected-(FSYNC_MUXA-C-Pad9)") (class "Default")
      (node (ref "FSYNC_MUX") (pin "9") (pinfunction "C_9") (pintype "input"))
    )
    (net (code "81") (name "unconnected-(FSYNC_MUXA-INH-Pad6)") (class "Default")
      (node (ref "FSYNC_MUX") (pin "6") (pinfunction "INH_6") (pintype "input"))
    )
    (net (code "82") (name "unconnected-(FSYNC_MUXA-X-Pad3)") (class "Default")
      (node (ref "FSYNC_MUX") (pin "3") (pinfunction "X_3") (pintype "bidirectional"))
    )
    (net (code "83") (name "unconnected-(IC1A-G-Pad13)") (class "Default")
      (node (ref "IC1") (pin "13") (pinfunction "G_13") (pintype "input"))
    )
    (net (code "84") (name "unconnected-(IC1A-QH*-Pad9)") (class "Default")
      (node (ref "IC1") (pin "9") (pinfunction "QH*_9") (pintype "tri_state"))
    )
    (net (code "85") (name "unconnected-(IC1A-SCL-Pad10)") (class "Default")
      (node (ref "IC1") (pin "10") (pinfunction "SCL_10") (pintype "input"))
    )
    (net (code "86") (name "unconnected-(IC2A-O-Pad3)") (class "Default")
      (node (ref "IC2") (pin "3") (pinfunction "O_3") (pintype "output"))
    )
    (net (code "87") (name "unconnected-(IC2B-O-Pad6)") (class "Default")
      (node (ref "IC2") (pin "6") (pinfunction "O_6") (pintype "output"))
    )
    (net (code "88") (name "unconnected-(IC2C-O-Pad8)") (class "Default")
      (node (ref "IC2") (pin "8") (pinfunction "O_8") (pintype "output"))
    )
    (net (code "89") (name "unconnected-(IC2D-O-Pad11)") (class "Default")
      (node (ref "IC2") (pin "11") (pinfunction "O_11") (pintype "output"))
    )
    (net (code "90") (name "unconnected-(IC3A-O-Pad3)") (class "Default")
      (node (ref "IC3") (pin "3") (pinfunction "O_3") (pintype "output"))
    )
    (net (code "91") (name "unconnected-(IC3B-O-Pad6)") (class "Default")
      (node (ref "IC3") (pin "6") (pinfunction "O_6") (pintype "output"))
    )
    (net (code "92") (name "unconnected-(IC3C-O-Pad8)") (class "Default")
      (node (ref "IC3") (pin "8") (pinfunction "O_8") (pintype "output"))
    )
    (net (code "93") (name "unconnected-(IC3D-O-Pad11)") (class "Default")
      (node (ref "IC3") (pin "11") (pinfunction "O_11") (pintype "output"))
    )
    (net (code "94") (name "unconnected-(IC4A-O-Pad3)") (class "Default")
      (node (ref "IC4") (pin "3") (pinfunction "O_3") (pintype "output"))
    )
    (net (code "95") (name "unconnected-(IC4B-O-Pad6)") (class "Default")
      (node (ref "IC4") (pin "6") (pinfunction "O_6") (pintype "output"))
    )
    (net (code "96") (name "unconnected-(IC4C-O-Pad8)") (class "Default")
      (node (ref "IC4") (pin "8") (pinfunction "O_8") (pintype "output"))
    )
    (net (code "97") (name "unconnected-(IC4D-O-Pad11)") (class "Default")
      (node (ref "IC4") (pin "11") (pinfunction "O_11") (pintype "output"))
    )
    (net (code "98") (name "unconnected-(IC5A-O-Pad3)") (class "Default")
      (node (ref "IC5") (pin "3") (pinfunction "O_3") (pintype "output"))
    )
    (net (code "99") (name "unconnected-(IC5B-O-Pad6)") (class "Default")
      (node (ref "IC5") (pin "6") (pinfunction "O_6") (pintype "output"))
    )
    (net (code "100") (name "unconnected-(IC5C-O-Pad8)") (class "Default")
      (node (ref "IC5") (pin "8") (pinfunction "O_8") (pintype "output"))
    )
    (net (code "101") (name "unconnected-(IC5D-O-Pad11)") (class "Default")
      (node (ref "IC5") (pin "11") (pinfunction "O_11") (pintype "output"))
    )
    (net (code "102") (name "unconnected-(IC6A-O-Pad3)") (class "Default")
      (node (ref "IC6") (pin "3") (pinfunction "O_3") (pintype "output"))
    )
    (net (code "103") (name "unconnected-(IC6B-O-Pad6)") (class "Default")
      (node (ref "IC6") (pin "6") (pinfunction "O_6") (pintype "output"))
    )
    (net (code "104") (name "unconnected-(IC6C-O-Pad8)") (class "Default")
      (node (ref "IC6") (pin "8") (pinfunction "O_8") (pintype "output"))
    )
    (net (code "105") (name "unconnected-(IC6D-O-Pad11)") (class "Default")
      (node (ref "IC6") (pin "11") (pinfunction "O_11") (pintype "output"))
    )
    (net (code "106") (name "unconnected-(IC7A-O-Pad3)") (class "Default")
      (node (ref "IC7") (pin "3") (pinfunction "O_3") (pintype "output"))
    )
    (net (code "107") (name "unconnected-(IC7B-O-Pad6)") (class "Default")
      (node (ref "IC7") (pin "6") (pinfunction "O_6") (pintype "output"))
    )
    (net (code "108") (name "unconnected-(IC7C-O-Pad8)") (class "Default")
      (node (ref "IC7") (pin "8") (pinfunction "O_8") (pintype "output"))
    )
    (net (code "109") (name "unconnected-(IC7D-O-Pad11)") (class "Default")
      (node (ref "IC7") (pin "11") (pinfunction "O_11") (pintype "output"))
    )
  )
)
